# drl.net
KiCad netlist of a schematic drawn in EAGLE
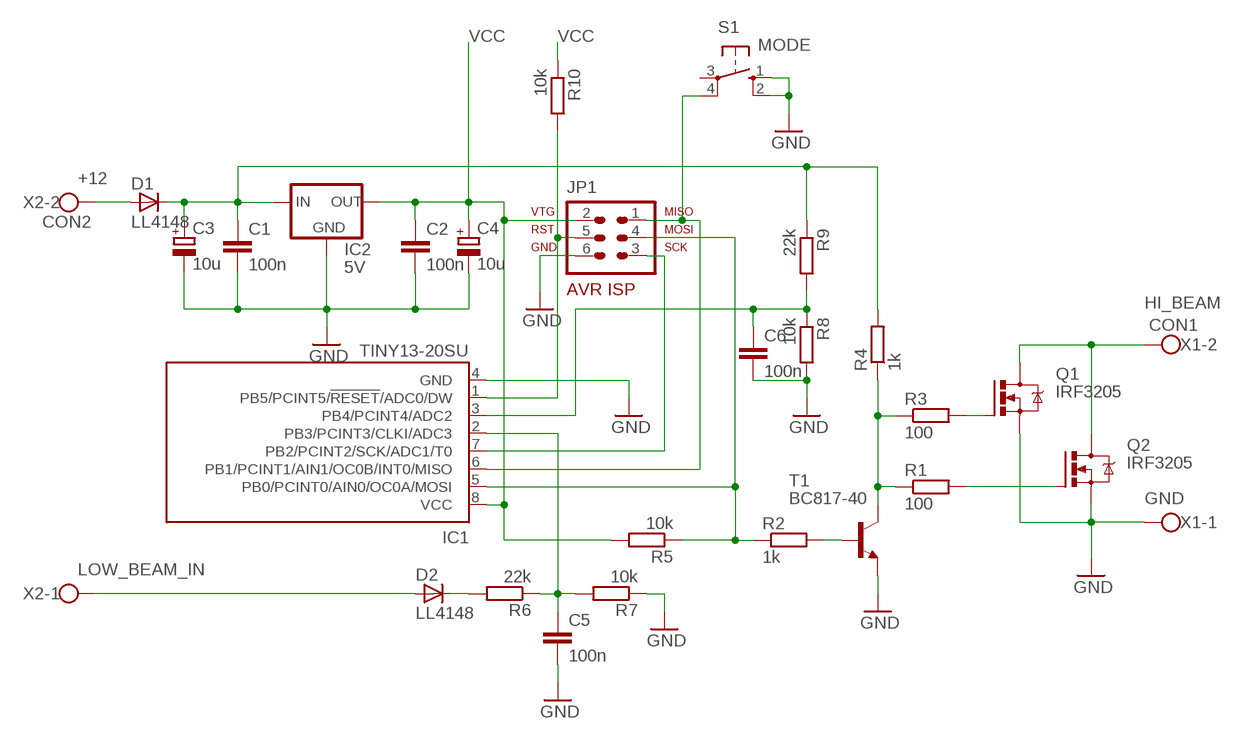
[diagram p0: schematic, sheet 1]

(export (version "E")
  (design (tool "Eeschema 10.0.6"))
  (components
    (comp (ref "C1")
      (value "100n")
      (footprint "eagle-import:C0805K")
      (libsource (lib "eagle-import") (part "C-EUC0805K"))
    )
    (comp (ref "C2")
      (value "100n")
      (footprint "eagle-import:C0805K")
      (libsource (lib "eagle-import") (part "C-EUC0805K"))
    )
    (comp (ref "C3")
      (value "10u")
      (footprint "eagle-import:SMC_D")
      (libsource (lib "eagle-import") (part "CPOL-EUSMCD"))
    )
    (comp (ref "C4")
      (value "10u")
      (footprint "eagle-import:SMC_D")
      (libsource (lib "eagle-import") (part "CPOL-EUSMCD"))
    )
    (comp (ref "C5")
      (value "100n")
      (footprint "eagle-import:C0805K")
      (libsource (lib "eagle-import") (part "C-EUC0805K"))
    )
    (comp (ref "C6")
      (value "100n")
      (footprint "eagle-import:C0805K")
      (libsource (lib "eagle-import") (part "C-EUC0805K"))
    )
    (comp (ref "D1")
      (value "LL4148")
      (footprint "eagle-import:SOD80")
      (libsource (lib "eagle-import") (part "D-SOD-80"))
    )
    (comp (ref "D2")
      (value "LL4148")
      (footprint "eagle-import:SOD80")
      (libsource (lib "eagle-import") (part "D-SOD-80"))
    )
    (comp (ref "IC1")
      (value "TINY13-20SU")
      (footprint "eagle-import:8S2")
      (fields (field (name "MPN") "ATTINY13-20SU"))
      (libsource (lib "eagle-import") (part "TINY13SU-20"))
    )
    (comp (ref "IC2")
      (value "5V")
      (footprint "eagle-import:SOIC8")
      (libsource (lib "eagle-import") (part "UA78L05SOIC"))
    )
    (comp (ref "JP1")
      (value "AVR-ISP-6")
      (footprint "eagle-import:AVR-ISP-6")
      (libsource (lib "eagle-import") (part "AVR-ISP-6"))
    )
    (comp (ref "Q1")
      (value "IRF3205")
      (footprint "eagle-import:TO220BV")
      (libsource (lib "eagle-import") (part "IRF3205"))
    )
    (comp (ref "Q2")
      (value "IRF3205")
      (footprint "eagle-import:TO220BV")
      (libsource (lib "eagle-import") (part "IRF3205"))
    )
    (comp (ref "R1")
      (value "100")
      (footprint "eagle-import:R0805")
      (libsource (lib "eagle-import") (part "R-EU_R0805"))
    )
    (comp (ref "R2")
      (value "1k")
      (footprint "eagle-import:0204_7")
      (libsource (lib "eagle-import") (part "R-EU_0204/7"))
    )
    (comp (ref "R3")
      (value "100")
      (footprint "eagle-import:R0805")
      (libsource (lib "eagle-import") (part "R-EU_R0805"))
    )
    (comp (ref "R4")
      (value "1k")
      (footprint "eagle-import:R0805")
      (libsource (lib "eagle-import") (part "R-EU_R0805"))
    )
    (comp (ref "R5")
      (value "10k")
      (footprint "eagle-import:R0805")
      (libsource (lib "eagle-import") (part "R-EU_R0805"))
    )
    (comp (ref "R6")
      (value "22k")
      (footprint "eagle-import:R0805")
      (libsource (lib "eagle-import") (part "R-EU_R0805"))
    )
    (comp (ref "R7")
      (value "10k")
      (footprint "eagle-import:R0805")
      (libsource (lib "eagle-import") (part "R-EU_R0805"))
    )
    (comp (ref "R8")
      (value "10k")
      (footprint "eagle-import:R0805")
      (libsource (lib "eagle-import") (part "R-EU_R0805"))
    )
    (comp (ref "R9")
      (value "22k")
      (footprint "eagle-import:R0805")
      (libsource (lib "eagle-import") (part "R-EU_R0805"))
    )
    (comp (ref "R10")
      (value "10k")
      (footprint "eagle-import:R0805")
      (libsource (lib "eagle-import") (part "R-EU_R0805"))
    )
    (comp (ref "S1")
      (value "MODE")
      (footprint "eagle-import:B3F-10XX")
      (fields (field (name "MPN") "B3F-1000"))
      (libsource (lib "eagle-import") (part "10-XX"))
    )
    (comp (ref "T1")
      (value "BC817-40")
      (footprint "eagle-import:SOT23-BEC")
      (libsource (lib "eagle-import") (part "-NPN-SOT23-BECBC817-40"))
    )
    (comp (ref "X1")
      (value "CON1")
      (footprint "eagle-import:W237-102")
      (fields (field (name "MPN") "237-102"))
      (libsource (lib "eagle-import") (part "W237-102"))
    )
    (comp (ref "X2")
      (value "CON2")
      (footprint "eagle-import:W237-102")
      (fields (field (name "MPN") "237-102"))
      (libsource (lib "eagle-import") (part "W237-102"))
    )
  )
  (nets
    (net (code "1") (name "/+12") (class "Default")
      (node (ref "D1") (pin "2") (pinfunction "A_2") (pintype "passive"))
      (node (ref "X2") (pin "2") (pinfunction "KL_2") (pintype "passive"))
    )
    (net (code "2") (name "/HI_BEAM") (class "Default")
      (node (ref "Q1") (pin "D") (pinfunction "D_D") (pintype "passive"))
      (node (ref "Q2") (pin "D") (pinfunction "D_D") (pintype "passive"))
      (node (ref "X1") (pin "2") (pinfunction "KL_2") (pintype "passive"))
    )
    (net (code "3") (name "/LOW_BEAM_IN") (class "Default")
      (node (ref "D2") (pin "2") (pinfunction "A_2") (pintype "passive"))
      (node (ref "X2") (pin "1") (pinfunction "KL_1") (pintype "passive"))
    )
    (net (code "4") (name "/VCC") (class "Default")
      (node (ref "C2") (pin "1") (pinfunction "1_1") (pintype "passive"))
      (node (ref "C4") (pin "+") (pinfunction "+_+") (pintype "passive"))
      (node (ref "IC1") (pin "8") (pinfunction "VCC_8") (pintype "power_in"))
      (node (ref "IC2") (pin "1") (pinfunction "OUT_1") (pintype "passive"))
      (node (ref "JP1") (pin "2") (pinfunction "2_2") (pintype "passive"))
      (node (ref "R10") (pin "1") (pinfunction "1_1") (pintype "passive"))
      (node (ref "R5") (pin "2") (pinfunction "2_2") (pintype "passive"))
    )
    (net (code "5") (name "GND") (class "Default")
      (node (ref "C1") (pin "2") (pinfunction "2_2") (pintype "passive"))
      (node (ref "C2") (pin "2") (pinfunction "2_2") (pintype "passive"))
      (node (ref "C3") (pin "-") (pinfunction "-_-") (pintype "passive"))
      (node (ref "C4") (pin "-") (pinfunction "-_-") (pintype "passive"))
      (node (ref "C5") (pin "2") (pinfunction "2_2") (pintype "passive"))
      (node (ref "C6") (pin "2") (pinfunction "2_2") (pintype "passive"))
      (node (ref "IC1") (pin "4") (pinfunction "GND_4") (pintype "power_in"))
      (node (ref "IC2") (pin "2") (pinfunction "GND_2") (pintype "input"))
      (node (ref "IC2") (pin "3") (pinfunction "GND_3") (pintype "input"))
      (node (ref "IC2") (pin "6") (pinfunction "GND_6") (pintype "input"))
      (node (ref "IC2") (pin "7") (pinfunction "GND_7") (pintype "input"))
      (node (ref "JP1") (pin "6") (pinfunction "6_6") (pintype "passive"))
      (node (ref "Q1") (pin "S") (pinfunction "S_S") (pintype "passive"))
      (node (ref "Q2") (pin "S") (pinfunction "S_S") (pintype "passive"))
      (node (ref "R7") (pin "1") (pinfunction "1_1") (pintype "passive"))
      (node (ref "R8") (pin "2") (pinfunction "2_2") (pintype "passive"))
      (node (ref "S1") (pin "1") (pinfunction "S_1") (pintype "passive"))
      (node (ref "S1") (pin "2") (pinfunction "S1_2") (pintype "passive"))
      (node (ref "T1") (pin "E") (pinfunction "E_E") (pintype "passive"))
      (node (ref "X1") (pin "1") (pinfunction "KL_1") (pintype "passive"))
    )
    (net (code "6") (name "Net-(D1-C)") (class "Default")
      (node (ref "C1") (pin "1") (pinfunction "1_1") (pintype "passive"))
      (node (ref "C3") (pin "+") (pinfunction "+_+") (pintype "passive"))
      (node (ref "D1") (pin "1") (pinfunction "C_1") (pintype "passive"))
      (node (ref "IC2") (pin "8") (pinfunction "IN_8") (pintype "input"))
      (node (ref "R4") (pin "2") (pinfunction "2_2") (pintype "passive"))
      (node (ref "R9") (pin "1") (pinfunction "1_1") (pintype "passive"))
    )
    (net (code "7") (name "Net-(D2-C)") (class "Default")
      (node (ref "D2") (pin "1") (pinfunction "C_1") (pintype "passive"))
      (node (ref "R6") (pin "2") (pinfunction "2_2") (pintype "passive"))
    )
    (net (code "8") (name "Net-(IC1-PB0{slash}PCINT0{slash}AIN0{slash}OC0A{slash}MOSI)") (class "Default")
      (node (ref "IC1") (pin "5") (pinfunction "PB0/PCINT0/AIN0/OC0A/MOSI_5") (pintype "bidirectional"))
      (node (ref "JP1") (pin "4") (pinfunction "4_4") (pintype "passive"))
      (node (ref "R2") (pin "1") (pinfunction "1_1") (pintype "passive"))
      (node (ref "R5") (pin "1") (pinfunction "1_1") (pintype "passive"))
    )
    (net (code "9") (name "Net-(IC1-PB1{slash}PCINT1{slash}AIN1{slash}OC0B{slash}INT0{slash}MISO)") (class "Default")
      (node (ref "IC1") (pin "6") (pinfunction "PB1/PCINT1/AIN1/OC0B/INT0/MISO_6") (pintype "bidirectional"))
      (node (ref "JP1") (pin "1") (pinfunction "1_1") (pintype "passive"))
      (node (ref "S1") (pin "4") (pinfunction "P1_4") (pintype "passive"))
    )
    (net (code "10") (name "Net-(IC1-PB2{slash}PCINT2{slash}SCK{slash}ADC1{slash}T0)") (class "Default")
      (node (ref "IC1") (pin "7") (pinfunction "PB2/PCINT2/SCK/ADC1/T0_7") (pintype "bidirectional"))
      (node (ref "JP1") (pin "3") (pinfunction "3_3") (pintype "passive"))
    )
    (net (code "11") (name "Net-(IC1-PB3{slash}PCINT3{slash}CLKI{slash}ADC3)") (class "Default")
      (node (ref "C5") (pin "1") (pinfunction "1_1") (pintype "passive"))
      (node (ref "IC1") (pin "2") (pinfunction "PB3/PCINT3/CLKI/ADC3_2") (pintype "bidirectional"))
      (node (ref "R6") (pin "1") (pinfunction "1_1") (pintype "passive"))
      (node (ref "R7") (pin "2") (pinfunction "2_2") (pintype "passive"))
    )
    (net (code "12") (name "Net-(IC1-PB4{slash}PCINT4{slash}ADC2)") (class "Default")
      (node (ref "C6") (pin "1") (pinfunction "1_1") (pintype "passive"))
      (node (ref "IC1") (pin "3") (pinfunction "PB4/PCINT4/ADC2_3") (pintype "bidirectional"))
      (node (ref "R8") (pin "1") (pinfunction "1_1") (pintype "passive"))
      (node (ref "R9") (pin "2") (pinfunction "2_2") (pintype "passive"))
    )
    (net (code "13") (name "Net-(IC1-PB5{slash}PCINT5{slash}~{RESET}{slash}ADC0{slash}DW)") (class "Default")
      (node (ref "IC1") (pin "1") (pinfunction "PB5/PCINT5/~{RESET}/ADC0/DW_1") (pintype "bidirectional"))
      (node (ref "JP1") (pin "5") (pinfunction "5_5") (pintype "passive"))
      (node (ref "R10") (pin "2") (pinfunction "2_2") (pintype "passive"))
    )
    (net (code "14") (name "Net-(Q1-PadG)") (class "Default")
      (node (ref "Q1") (pin "G") (pinfunction "G_G") (pintype "passive"))
      (node (ref "R3") (pin "2") (pinfunction "2_2") (pintype "passive"))
    )
    (net (code "15") (name "Net-(Q2-PadG)") (class "Default")
      (node (ref "Q2") (pin "G") (pinfunction "G_G") (pintype "passive"))
      (node (ref "R1") (pin "2") (pinfunction "2_2") (pintype "passive"))
    )
    (net (code "16") (name "Net-(R1-Pad1)") (class "Default")
      (node (ref "R1") (pin "1") (pinfunction "1_1") (pintype "passive"))
      (node (ref "R3") (pin "1") (pinfunction "1_1") (pintype "passive"))
      (node (ref "R4") (pin "1") (pinfunction "1_1") (pintype "passive"))
      (node (ref "T1") (pin "C") (pinfunction "C_C") (pintype "passive"))
    )
    (net (code "17") (name "Net-(R2-Pad2)") (class "Default")
      (node (ref "R2") (pin "2") (pinfunction "2_2") (pintype "passive"))
      (node (ref "T1") (pin "B") (pinfunction "B_B") (pintype "passive"))
    )
    (net (code "18") (name "unconnected-(S1-P-Pad3)") (class "Default")
      (node (ref "S1") (pin "3") (pinfunction "P_3") (pintype "passive"))
    )
  )
)
